# 01_Power.net
KiCad netlist of a schematic drawn in Altium Designer
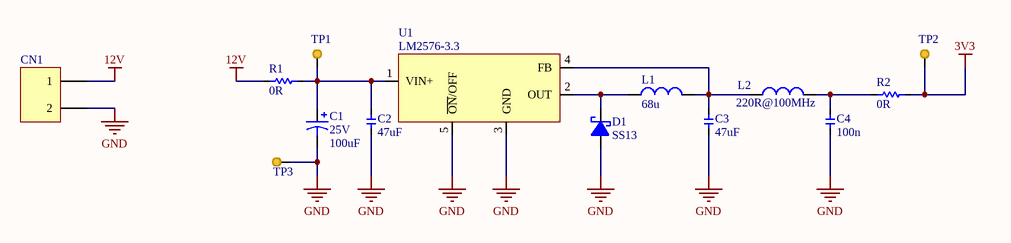
[diagram p0: 01_Power.SchDoc]

(export (version "E")
  (design (tool "Eeschema 10.0.6"))
  (components
    (comp (ref "C1")
      (value "25V")
      (footprint "Moji Footprintovi:Electrolytic Cap 2.54mm")
      (description "CAP ALUM 100UF 20% 25V RADIAL")
      (fields
        (field (name "MANUFACTURER") "Nichicon")
        (field (name "MANUFACTURER PART NUMBER") "UHE1E101MED")
        (field (name "ALTIUM_VALUE") "100uF")
      )
      (libsource (lib "Moji Schematici") (part "Cap Electrolytic"))
    )
    (comp (ref "C2")
      (value "47uF")
      (footprint "Moji Footprintovi:CAPC_1411_3528_X08N")
      (description "CAP TANT POLY47UF 20% 16V 1210")
      (fields
        (field (name "MANUFACTURER") "AVX Corporation")
        (field (name "MANUFACTURER PART NUMBER") "TCNT476M016R0200A")
      )
      (libsource (lib "Moji Schematici") (part "Cap"))
    )
    (comp (ref "C3")
      (value "47uF")
      (footprint "Moji Footprintovi:CAPC_1411_3528_X08N")
      (description "CAP TANT POLY47UF 20% 16V 1210")
      (fields
        (field (name "MANUFACTURER") "AVX Corporation")
        (field (name "MANUFACTURER PART NUMBER") "TCNT476M016R0200A")
      )
      (libsource (lib "Moji Schematici") (part "Cap"))
    )
    (comp (ref "C4")
      (value "100n")
      (footprint "Moji Footprintovi:0603 - CAP")
      (description "Capacitor")
      (fields
        (field (name "MANUFACTURER") "AVX Corporation")
        (field (name "MANUFACTURER PART NUMBER") "06035C104KAT2A")
      )
      (libsource (lib "Moji Schematici") (part "Cap"))
    )
    (comp (ref "CN1")
      (value "Terminal 2 - 5mm")
      (footprint "Moji Footprintovi:Terminal 2")
      (description "TERM BLOCK PCB 2POS 5.0MM GREEN")
      (fields
        (field (name "MANUFACTURER") "Phoenix Contact")
        (field (name "MANUFACTURER PART NUMBER") "1935161")
      )
      (libsource (lib "Moji Schematici") (part "Terminal 2"))
    )
    (comp (ref "D1")
      (value "SS13")
      (footprint "Moji Footprintovi:SOD123F")
      (description "DIODE SCHOTTKY 30V 1A SMA")
      (fields
        (field (name "MANUFACTURER") "ON Semiconductor")
        (field (name "DISTRIBUTOR PART NUMBER") "SS13FSCT-ND")
      )
      (libsource (lib "Moji Schematici") (part "Diode Schotky"))
    )
    (comp (ref "L1")
      (value "68u")
      (footprint "Moji Footprintovi:IND_TH_SMD")
      (description "FIXED IND 68UH 1A 289 MOHM SMD")
      (fields
        (field (name "MANUFACTURER") "Laird-Signal Integrity Products")
        (field (name "MANUFACTURER PART NUMBER") "TYS6045680M-10")
      )
      (libsource (lib "Moji Schematici") (part "Inductor"))
    )
    (comp (ref "L2")
      (value "220R@100MHz")
      (footprint "Moji Footprintovi:0603")
      (description "FERRITE BEAD 220 OHM 0603 1LN")
      (fields
        (field (name "MANUFACTURER") "Murata Electronics North America")
        (field (name "MANUFACTURER PART NUMBER") "BLM18KG221SN1D")
      )
      (libsource (lib "Moji Schematici") (part "Inductor"))
    )
    (comp (ref "R1")
      (value "0R")
      (footprint "Moji Footprintovi:0603")
      (description "Resistor")
      (fields
        (field (name "MANUFACTURER") "Yageo")
        (field (name "MANUFACTURER PART NUMBER") "RC0603JR-070RL")
      )
      (libsource (lib "Moji Schematici") (part "Res"))
    )
    (comp (ref "R2")
      (value "0R")
      (footprint "Moji Footprintovi:0603")
      (description "Resistor")
      (fields
        (field (name "MANUFACTURER") "Yageo")
        (field (name "MANUFACTURER PART NUMBER") "RC0603JR-070RL")
      )
      (libsource (lib "Moji Schematici") (part "Res"))
    )
    (comp (ref "TP1")
      (value "Test Point 0.6mm")
      (footprint "Moji Footprintovi:TP_SMD_1mm")
      (libsource (lib "Moji Schematici") (part "TP"))
    )
    (comp (ref "TP2")
      (value "Test Point 0.6mm")
      (footprint "Moji Footprintovi:TP_SMD_1mm")
      (libsource (lib "Moji Schematici") (part "TP"))
    )
    (comp (ref "TP3")
      (value "Test Point 0.6mm")
      (footprint "Moji Footprintovi:TP_SMD_1mm")
      (libsource (lib "Moji Schematici") (part "TP"))
    )
    (comp (ref "U1")
      (value "LM2576-3.3")
      (footprint "Moji Footprintovi:TO263-5")
      (description "Switching mode regulator [ 3v3, 5v, 12v and ADJ ]")
      (fields
        (field (name "DISTRIBUTOR PART NUMBER") "LM2576-3.3WU-ND")
        (field (name "MANUFACTURER") "Microchip Technology")
      )
      (libsource (lib "Moji Schematici") (part "LM2576-xx"))
    )
  )
  (nets
    (net (code "1") (name "3V3") (class "Default")
      (node (ref "R2") (pin "1") (pinfunction "1_1") (pintype "passive"))
      (node (ref "TP2") (pin "1") (pinfunction "1_1") (pintype "passive"))
    )
    (net (code "2") (name "12V") (class "Default")
      (node (ref "CN1") (pin "1") (pinfunction "1_1") (pintype "passive"))
      (node (ref "R1") (pin "2") (pinfunction "2_2") (pintype "passive"))
    )
    (net (code "3") (name "GND") (class "Default")
      (node (ref "C1") (pin "2") (pinfunction "2_2") (pintype "passive"))
      (node (ref "C2") (pin "1") (pinfunction "1_1") (pintype "passive"))
      (node (ref "C3") (pin "1") (pinfunction "1_1") (pintype "passive"))
      (node (ref "C4") (pin "1") (pinfunction "1_1") (pintype "passive"))
      (node (ref "CN1") (pin "2") (pinfunction "2_2") (pintype "passive"))
      (node (ref "D1") (pin "A") (pinfunction "A_A") (pintype "passive"))
      (node (ref "TP3") (pin "1") (pinfunction "1_1") (pintype "passive"))
      (node (ref "U1") (pin "3") (pinfunction "GND_3") (pintype "passive"))
      (node (ref "U1") (pin "5") (pinfunction "~{ON}/OFF_5") (pintype "passive"))
    )
    (net (code "4") (name "Net-(C4-Pad2)") (class "Default")
      (node (ref "C4") (pin "2") (pinfunction "2_2") (pintype "passive"))
      (node (ref "L2") (pin "2") (pinfunction "2_2") (pintype "passive"))
      (node (ref "R2") (pin "2") (pinfunction "2_2") (pintype "passive"))
    )
    (net (code "5") (name "Net-(U1-FB)") (class "Default")
      (node (ref "C3") (pin "2") (pinfunction "2_2") (pintype "passive"))
      (node (ref "L1") (pin "2") (pinfunction "2_2") (pintype "passive"))
      (node (ref "L2") (pin "1") (pinfunction "1_1") (pintype "passive"))
      (node (ref "U1") (pin "4") (pinfunction "FB_4") (pintype "passive"))
    )
    (net (code "6") (name "Net-(U1-OUT)") (class "Default")
      (node (ref "D1") (pin "K") (pinfunction "K_K") (pintype "passive"))
      (node (ref "L1") (pin "1") (pinfunction "1_1") (pintype "passive"))
      (node (ref "U1") (pin "2") (pinfunction "OUT_2") (pintype "passive"))
    )
    (net (code "7") (name "Net-(U1-VIN+)") (class "Default")
      (node (ref "C1") (pin "1") (pinfunction "1_1") (pintype "passive"))
      (node (ref "C2") (pin "2") (pinfunction "2_2") (pintype "passive"))
      (node (ref "R1") (pin "1") (pinfunction "1_1") (pintype "passive"))
      (node (ref "TP1") (pin "1") (pinfunction "1_1") (pintype "passive"))
      (node (ref "U1") (pin "1") (pinfunction "VIN+_1") (pintype "passive"))
    )
  )
)
